# Schematic.net
KiCad netlist of a schematic drawn in EAGLE
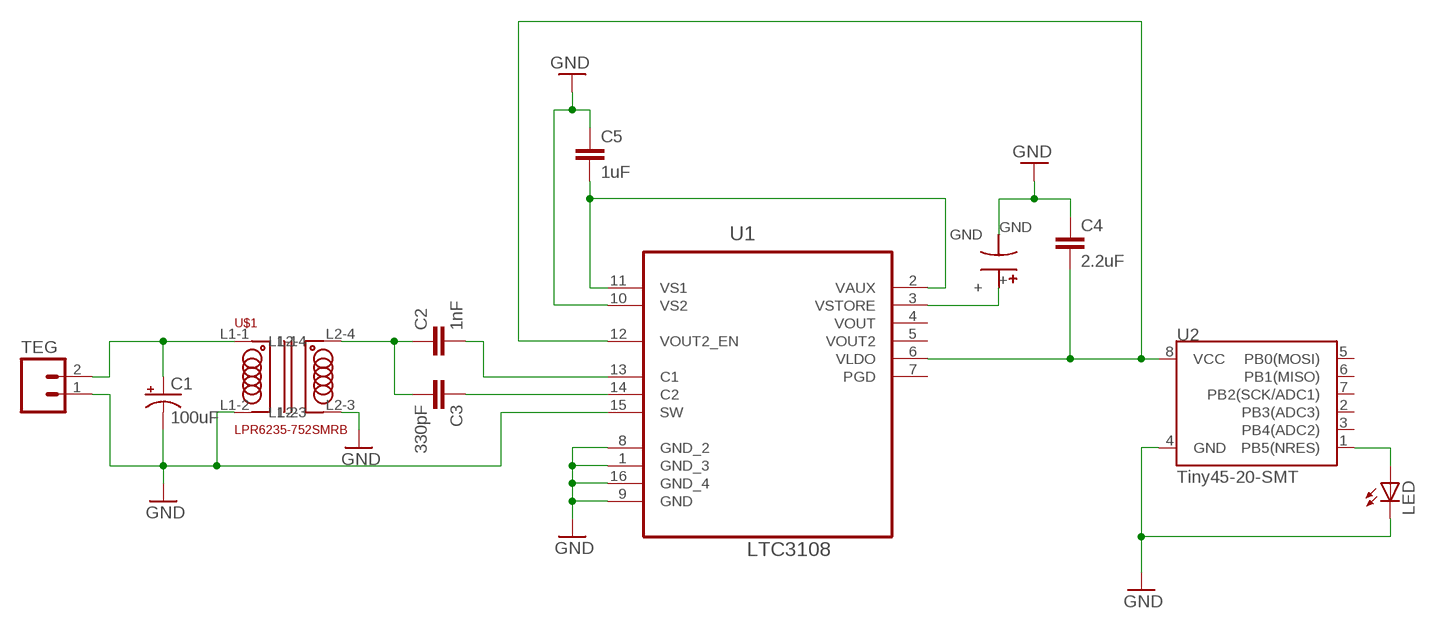
[diagram p0: schematic, sheet 1]

(export (version "E")
  (design (tool "Eeschema 10.0.6"))
  (components
    (comp (ref "C1")
      (value "100uF")
      (footprint "eagle-import:EIA3216")
      (libsource (lib "eagle-import") (part "10UF-16V-10%(TANT)"))
    )
    (comp (ref "C2")
      (value "1nF")
      (footprint "eagle-import:0603-CAP")
      (libsource (lib "eagle-import") (part "CAP0603-CAP"))
    )
    (comp (ref "C3")
      (value "330pF")
      (footprint "eagle-import:0603-CAP")
      (libsource (lib "eagle-import") (part "CAP0603-CAP"))
    )
    (comp (ref "C4")
      (value "2.2uF")
      (footprint "eagle-import:0603-CAP")
      (libsource (lib "eagle-import") (part "CAP0603-CAP"))
    )
    (comp (ref "C5")
      (value "1uF")
      (footprint "eagle-import:0603-CAP")
      (libsource (lib "eagle-import") (part "CAP0603-CAP"))
    )
    (comp (ref "C6")
      (value "FC0V104FTBR24")
      (footprint "eagle-import:FC0V104ZFTBR24")
      (libsource (lib "eagle-import") (part "FC0V104FTBR24"))
    )
    (comp (ref "LED")
      (value "LEDCHIPLED_0805")
      (footprint "eagle-import:CHIPLED_0805")
      (libsource (lib "eagle-import") (part "LEDCHIPLED_0805"))
    )
    (comp (ref "TEG")
      (value "M02LOCK")
      (footprint "eagle-import:1X02_LOCK")
      (libsource (lib "eagle-import") (part "M02LOCK"))
    )
    (comp (ref "U$1")
      (value "LPR6235-752SMRB")
      (footprint "eagle-import:LPR6235-752SMRB")
      (libsource (lib "eagle-import") (part "LPR6235-752SMRB"))
    )
    (comp (ref "U1")
      (value "LTC3108")
      (footprint "eagle-import:SOP63P600X175-16N")
      (fields (field (name "MPN") "LTC3108IGN#PBF"))
      (libsource (lib "eagle-import") (part "LTC3108IGNPBF"))
    )
    (comp (ref "U2")
      (value "Tiny45-20-SMT")
      (footprint "eagle-import:SO08-EIAJ")
      (libsource (lib "eagle-import") (part "ATTINY45TINY45-20-SMT"))
    )
  )
  (nets
    (net (code "1") (name "GND") (class "Default")
      (node (ref "C1") (pin "C") (pinfunction "-_C") (pintype "passive"))
      (node (ref "C4") (pin "1") (pinfunction "1_1") (pintype "passive"))
      (node (ref "C5") (pin "1") (pinfunction "1_1") (pintype "passive"))
      (node (ref "C6") (pin "GND") (pinfunction "GND_GND") (pintype "bidirectional"))
      (node (ref "LED") (pin "C") (pinfunction "C_C") (pintype "passive"))
      (node (ref "TEG") (pin "1") (pinfunction "1_1") (pintype "passive"))
      (node (ref "U$1") (pin "L1-2") (pinfunction "L1-2_L1-2") (pintype "bidirectional"))
      (node (ref "U$1") (pin "L2-3") (pinfunction "L2-3_L2-3") (pintype "bidirectional"))
      (node (ref "U1") (pin "1") (pinfunction "GND_3_1") (pintype "passive"))
      (node (ref "U1") (pin "10") (pinfunction "VS2_10") (pintype "input"))
      (node (ref "U1") (pin "15") (pinfunction "SW_15") (pintype "passive"))
      (node (ref "U1") (pin "16") (pinfunction "GND_4_16") (pintype "passive"))
      (node (ref "U1") (pin "8") (pinfunction "GND_2_8") (pintype "passive"))
      (node (ref "U1") (pin "9") (pinfunction "GND_9") (pintype "passive"))
      (node (ref "U2") (pin "4") (pinfunction "GND_4") (pintype "bidirectional"))
    )
    (net (code "2") (name "Net-(C1-+)") (class "Default")
      (node (ref "C1") (pin "A") (pinfunction "+_A") (pintype "passive"))
      (node (ref "TEG") (pin "2") (pinfunction "2_2") (pintype "passive"))
      (node (ref "U$1") (pin "L1-1") (pinfunction "L1-1_L1-1") (pintype "bidirectional"))
    )
    (net (code "3") (name "Net-(C2-Pad1)") (class "Default")
      (node (ref "C2") (pin "1") (pinfunction "1_1") (pintype "passive"))
      (node (ref "C3") (pin "2") (pinfunction "2_2") (pintype "passive"))
      (node (ref "U$1") (pin "L2-4") (pinfunction "L2-4_L2-4") (pintype "bidirectional"))
    )
    (net (code "4") (name "Net-(U1-C1)") (class "Default")
      (node (ref "C2") (pin "2") (pinfunction "2_2") (pintype "passive"))
      (node (ref "U1") (pin "13") (pinfunction "C1_13") (pintype "input"))
    )
    (net (code "5") (name "Net-(U1-C2)") (class "Default")
      (node (ref "C3") (pin "1") (pinfunction "1_1") (pintype "passive"))
      (node (ref "U1") (pin "14") (pinfunction "C2_14") (pintype "input"))
    )
    (net (code "6") (name "Net-(U1-VAUX)") (class "Default")
      (node (ref "C5") (pin "2") (pinfunction "2_2") (pintype "passive"))
      (node (ref "U1") (pin "11") (pinfunction "VS1_11") (pintype "input"))
      (node (ref "U1") (pin "2") (pinfunction "VAUX_2") (pintype "output"))
    )
    (net (code "7") (name "Net-(U1-VLDO)") (class "Default")
      (node (ref "C4") (pin "2") (pinfunction "2_2") (pintype "passive"))
      (node (ref "U1") (pin "12") (pinfunction "VOUT2_EN_12") (pintype "input"))
      (node (ref "U1") (pin "6") (pinfunction "VLDO_6") (pintype "output"))
      (node (ref "U2") (pin "8") (pinfunction "VCC_8") (pintype "bidirectional"))
    )
    (net (code "8") (name "Net-(U1-VSTORE)") (class "Default")
      (node (ref "C6") (pin "+") (pinfunction "+_+") (pintype "bidirectional"))
      (node (ref "U1") (pin "3") (pinfunction "VSTORE_3") (pintype "output"))
    )
    (net (code "9") (name "Net-(U2-PB5(NRES))") (class "Default")
      (node (ref "LED") (pin "A") (pinfunction "A_A") (pintype "passive"))
      (node (ref "U2") (pin "1") (pinfunction "PB5(NRES)_1") (pintype "bidirectional"))
    )
    (net (code "10") (name "unconnected-(U1-PGD-Pad7)") (class "Default")
      (node (ref "U1") (pin "7") (pinfunction "PGD_7") (pintype "output"))
    )
    (net (code "11") (name "unconnected-(U1-VOUT-Pad4)") (class "Default")
      (node (ref "U1") (pin "4") (pinfunction "VOUT_4") (pintype "output"))
    )
    (net (code "12") (name "unconnected-(U1-VOUT2-Pad5)") (class "Default")
      (node (ref "U1") (pin "5") (pinfunction "VOUT2_5") (pintype "output"))
    )
    (net (code "13") (name "unconnected-(U2-PB0(MOSI)-Pad5)") (class "Default")
      (node (ref "U2") (pin "5") (pinfunction "PB0(MOSI)_5") (pintype "bidirectional"))
    )
    (net (code "14") (name "unconnected-(U2-PB1(MISO)-Pad6)") (class "Default")
      (node (ref "U2") (pin "6") (pinfunction "PB1(MISO)_6") (pintype "bidirectional"))
    )
    (net (code "15") (name "unconnected-(U2-PB2(SCK{slash}ADC1)-Pad7)") (class "Default")
      (node (ref "U2") (pin "7") (pinfunction "PB2(SCK/ADC1)_7") (pintype "bidirectional"))
    )
    (net (code "16") (name "unconnected-(U2-PB3(ADC3)-Pad2)") (class "Default")
      (node (ref "U2") (pin "2") (pinfunction "PB3(ADC3)_2") (pintype "bidirectional"))
    )
    (net (code "17") (name "unconnected-(U2-PB4(ADC2)-Pad3)") (class "Default")
      (node (ref "U2") (pin "3") (pinfunction "PB4(ADC2)_3") (pintype "bidirectional"))
    )
  )
)
